# Navigation_switches.net
KiCad netlist of a schematic drawn in Altium Designer
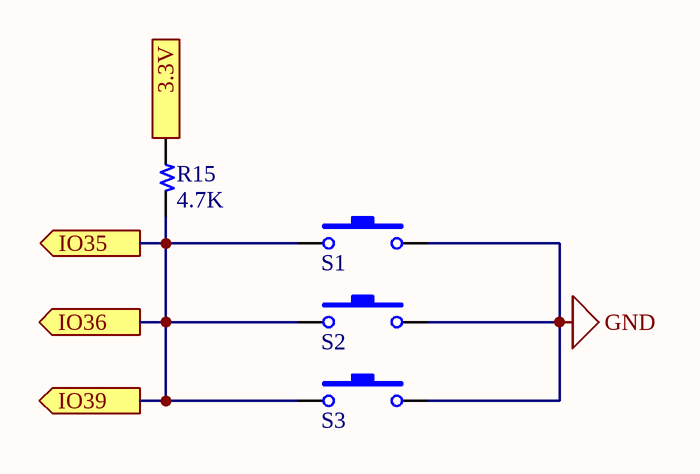
[diagram p0: Navigation switches.SchDoc]

(export (version "E")
  (design (tool "Eeschema 10.0.6"))
  (components
    (comp (ref "R15")
      (value "4.7K")
      (footprint "R 0805")
      (description "Resistor")
      (libsource (lib "chipfc_libs") (part "Resistor"))
    )
    (comp (ref "S1")
      (value "SW-SMD")
      (footprint "SW-SMD")
      (description "Switch")
      (fields (field (name "PUBLISHER") "Altium Limited"))
      (libsource (lib "Devzone_SCHLib") (part "SW-SMD"))
    )
    (comp (ref "S2")
      (value "SW-SMD")
      (footprint "SW-SMD")
      (description "Switch")
      (fields (field (name "PUBLISHER") "Altium Limited"))
      (libsource (lib "Devzone_SCHLib") (part "SW-SMD"))
    )
    (comp (ref "S3")
      (value "SW-SMD")
      (footprint "SW-SMD")
      (description "Switch")
      (fields (field (name "PUBLISHER") "Altium Limited"))
      (libsource (lib "Devzone_SCHLib") (part "SW-SMD"))
    )
  )
  (nets
    (net (code "1") (name "/3.3V") (class "Default")
      (node (ref "R15") (pin "1") (pinfunction "1_1") (pintype "passive"))
    )
    (net (code "2") (name "/IO35") (class "Default")
      (node (ref "R15") (pin "2") (pinfunction "2_2") (pintype "passive"))
      (node (ref "S1") (pin "1") (pinfunction "1_1") (pintype "passive"))
      (node (ref "S2") (pin "1") (pinfunction "1_1") (pintype "passive"))
      (node (ref "S3") (pin "1") (pinfunction "1_1") (pintype "passive"))
    )
    (net (code "3") (name "GND") (class "Default")
      (node (ref "S1") (pin "2") (pinfunction "2_2") (pintype "passive"))
      (node (ref "S2") (pin "2") (pinfunction "2_2") (pintype "passive"))
      (node (ref "S3") (pin "2") (pinfunction "2_2") (pintype "passive"))
    )
  )
)
